# principal.net
KiCad netlist of a schematic drawn in Altium Designer
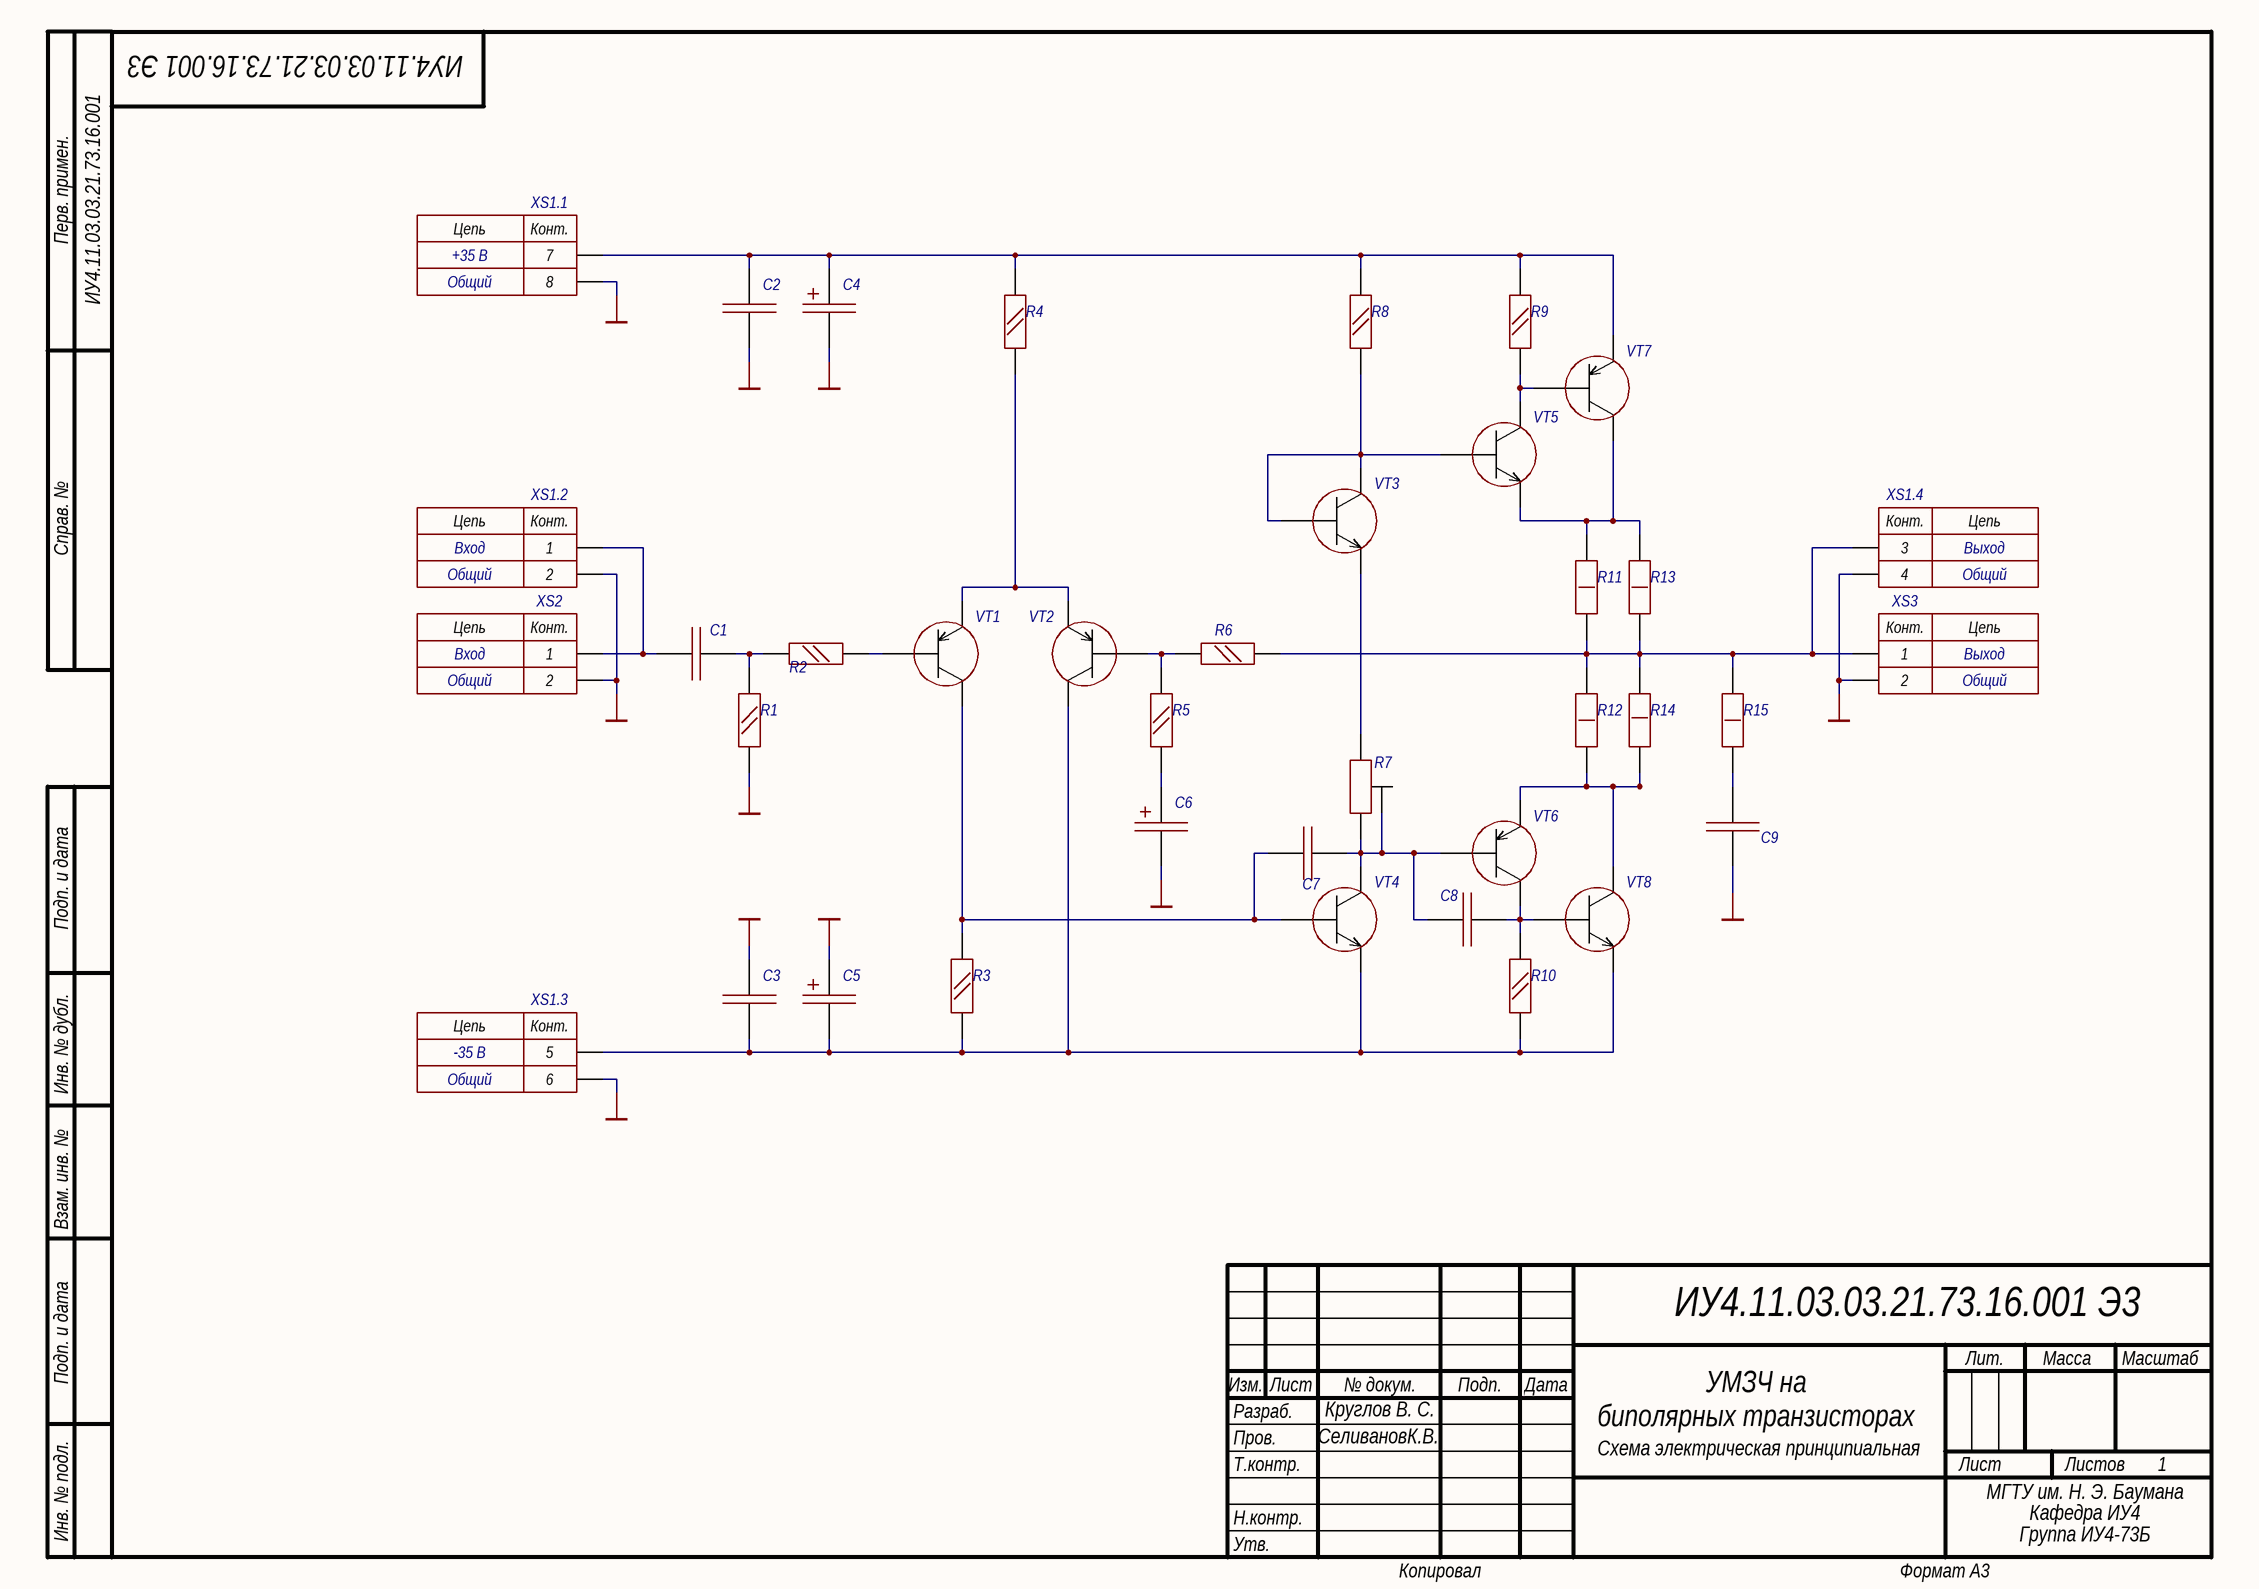
[diagram p0: principal.SchDoc]

(export (version "E")
  (design (tool "Eeschema 10.0.6"))
  (components
    (comp (ref "C1")
      (value "Capacitor")
      (footprint "CAP: 0805")
      (libsource (lib "Integrated_Library_PAAF") (part "Capacitor"))
    )
    (comp (ref "C2")
      (value "Capacitor")
      (footprint "CAP: 0805")
      (libsource (lib "Integrated_Library_PAAF") (part "Capacitor"))
    )
    (comp (ref "C3")
      (value "Capacitor")
      (footprint "CAP: 0805")
      (libsource (lib "Integrated_Library_PAAF") (part "Capacitor"))
    )
    (comp (ref "C4")
      (value "Capactor polar")
      (footprint "CAP: TANTAL-D")
      (libsource (lib "Integrated_Library_PAAF") (part "Capactor polar"))
    )
    (comp (ref "C5")
      (value "Capactor polar")
      (footprint "CAP: TANTAL-D")
      (libsource (lib "Integrated_Library_PAAF") (part "Capactor polar"))
    )
    (comp (ref "C6")
      (value "Capactor polar")
      (footprint "CAP: TANTAL-D")
      (libsource (lib "Integrated_Library_PAAF") (part "Capactor polar"))
    )
    (comp (ref "C7")
      (value "Capacitor")
      (footprint "CAP: 0805")
      (libsource (lib "Integrated_Library_PAAF") (part "Capacitor"))
    )
    (comp (ref "C8")
      (value "Capacitor")
      (footprint "CAP: 0805")
      (libsource (lib "Integrated_Library_PAAF") (part "Capacitor"))
    )
    (comp (ref "C9")
      (value "Capacitor")
      (footprint "CAP: 0805")
      (libsource (lib "Integrated_Library_PAAF") (part "Capacitor"))
    )
    (comp (ref "R1")
      (value "Resistor")
      (footprint "RES: 0805")
      (fields (field (name "TOLERANCE") "5%"))
      (libsource (lib "Sch") (part "Resistor"))
    )
    (comp (ref "R2")
      (value "Resistor")
      (footprint "RES: 0805")
      (fields (field (name "TOLERANCE") "5%"))
      (libsource (lib "") (part "Resistor_1"))
    )
    (comp (ref "R3")
      (value "Resistor")
      (footprint "RES: 0805")
      (fields (field (name "TOLERANCE") "5%"))
      (libsource (lib "Sch") (part "Resistor"))
    )
    (comp (ref "R4")
      (value "Resistor")
      (footprint "RES: 0805")
      (fields (field (name "TOLERANCE") "5%"))
      (libsource (lib "Sch") (part "Resistor"))
    )
    (comp (ref "R5")
      (value "Resistor")
      (footprint "RES: 0805")
      (fields (field (name "TOLERANCE") "5%"))
      (libsource (lib "Sch") (part "Resistor"))
    )
    (comp (ref "R6")
      (value "Resistor")
      (footprint "RES: 0805")
      (fields (field (name "TOLERANCE") "5%"))
      (libsource (lib "") (part "Resistor_1"))
    )
    (comp (ref "R7")
      (value "POT")
      (footprint "POT_3296W")
      (libsource (lib "Integrated_Library_PAAF") (part "POT"))
    )
    (comp (ref "R8")
      (value "Resistor")
      (footprint "RES: 0805")
      (fields (field (name "TOLERANCE") "5%"))
      (libsource (lib "Sch") (part "Resistor"))
    )
    (comp (ref "R9")
      (value "Resistor")
      (footprint "RES: 0805")
      (fields (field (name "TOLERANCE") "5%"))
      (libsource (lib "") (part "Resistor_2"))
    )
    (comp (ref "R10")
      (value "Resistor")
      (footprint "RES: 0805")
      (fields (field (name "TOLERANCE") "5%"))
      (libsource (lib "Sch") (part "Resistor"))
    )
    (comp (ref "R11")
      (value "Resistor")
      (footprint "RES: 2512")
      (fields (field (name "TOLERANCE") "5%"))
      (libsource (lib "Sch") (part "Resistor"))
    )
    (comp (ref "R12")
      (value "Resistor")
      (footprint "RES: 2512")
      (fields (field (name "TOLERANCE") "5%"))
      (libsource (lib "Sch") (part "Resistor"))
    )
    (comp (ref "R13")
      (value "Resistor")
      (footprint "RES: 2512")
      (fields (field (name "TOLERANCE") "5%"))
      (libsource (lib "Sch") (part "Resistor"))
    )
    (comp (ref "R14")
      (value "Resistor")
      (footprint "RES: 2512")
      (fields (field (name "TOLERANCE") "5%"))
      (libsource (lib "Sch") (part "Resistor"))
    )
    (comp (ref "R15")
      (value "Resistor")
      (footprint "RES: 2512")
      (fields (field (name "TOLERANCE") "5%"))
      (libsource (lib "Sch") (part "Resistor"))
    )
    (comp (ref "VT1")
      (value "Transistor_PNP")
      (footprint "TO92_3FB")
      (libsource (lib "Sch") (part "Transistor_PNP"))
    )
    (comp (ref "VT2")
      (value "Transistor_PNP")
      (footprint "TO92_3FB")
      (libsource (lib "Sch") (part "Transistor_PNP"))
    )
    (comp (ref "VT3")
      (value "BD139G")
      (footprint "TO126_3")
      (libsource (lib "Components - 07.07.24 - 21.07") (part "Transistor_NPN"))
    )
    (comp (ref "VT4")
      (value "BD139G")
      (footprint "TO220_3")
      (libsource (lib "Components - 07.07.24 - 21.07") (part "Transistor_NPN"))
    )
    (comp (ref "VT5")
      (value "BD139G")
      (footprint "TO126_3")
      (libsource (lib "Components - 07.07.24 - 21.07") (part "Transistor_NPN"))
    )
    (comp (ref "VT6")
      (value "Transistor_PNP")
      (footprint "TO126_3")
      (libsource (lib "Sch") (part "Transistor_PNP"))
    )
    (comp (ref "VT7")
      (value "Transistor_PNP")
      (footprint "TO247_3")
      (libsource (lib "Sch") (part "Transistor_PNP"))
    )
    (comp (ref "VT8")
      (value "BD139G")
      (footprint "TO247_3")
      (libsource (lib "Components - 07.07.24 - 21.07") (part "Transistor_NPN"))
    )
    (comp (ref "XP1") (value "CONN") (footprint "MOLEX_430450821") (libsource (lib "Sch") (part "CONN")))
    (comp (ref "XS1") (value "Audio") (footprint "FP-NMJ4HFD2-MFG") (libsource (lib "Sch") (part "Audio")))
    (comp (ref "XS2") (value "Audio") (footprint "FP-NMJ4HFD2-MFG") (libsource (lib "Sch") (part "Audio")))
  )
  (nets
    (net (code "1") (name "GND") (class "Default")
      (node (ref "C2") (pin "1") (pinfunction "1_1") (pintype "passive"))
      (node (ref "C3") (pin "2") (pinfunction "2_2") (pintype "passive"))
      (node (ref "C4") (pin "1") (pinfunction "1_1") (pintype "passive"))
      (node (ref "C5") (pin "2") (pinfunction "2_2") (pintype "passive"))
      (node (ref "C6") (pin "1") (pinfunction "1_1") (pintype "passive"))
      (node (ref "C9") (pin "2") (pinfunction "2_2") (pintype "passive"))
      (node (ref "R1") (pin "2") (pinfunction "2_2") (pintype "passive"))
      (node (ref "XP1") (pin "2") (pintype "passive"))
      (node (ref "XP1") (pin "4") (pintype "passive"))
      (node (ref "XP1") (pin "6") (pintype "passive"))
      (node (ref "XP1") (pin "8") (pintype "passive"))
      (node (ref "XS1") (pin "2") (pintype "passive"))
      (node (ref "XS2") (pin "2") (pintype "passive"))
    )
    (net (code "2") (name "Net-(C1-Pad1)") (class "Default")
      (node (ref "C1") (pin "1") (pinfunction "1_1") (pintype "passive"))
      (node (ref "XP1") (pin "1") (pintype "passive"))
      (node (ref "XS1") (pin "1") (pintype "passive"))
    )
    (net (code "3") (name "Net-(C1-Pad2)") (class "Default")
      (node (ref "C1") (pin "2") (pinfunction "2_2") (pintype "passive"))
      (node (ref "R1") (pin "1") (pinfunction "1_1") (pintype "passive"))
      (node (ref "R2") (pin "1") (pinfunction "1_1") (pintype "passive"))
    )
    (net (code "4") (name "Net-(C6-Pad2)") (class "Default")
      (node (ref "C6") (pin "2") (pinfunction "2_2") (pintype "passive"))
      (node (ref "R5") (pin "2") (pinfunction "2_2") (pintype "passive"))
    )
    (net (code "5") (name "Net-(C9-Pad1)") (class "Default")
      (node (ref "C9") (pin "1") (pinfunction "1_1") (pintype "passive"))
      (node (ref "R15") (pin "2") (pinfunction "2_2") (pintype "passive"))
    )
    (net (code "6") (name "Net-(R11-Pad2)") (class "Default")
      (node (ref "R11") (pin "2") (pinfunction "2_2") (pintype "passive"))
      (node (ref "R12") (pin "1") (pinfunction "1_1") (pintype "passive"))
      (node (ref "R13") (pin "2") (pinfunction "2_2") (pintype "passive"))
      (node (ref "R14") (pin "1") (pinfunction "1_1") (pintype "passive"))
      (node (ref "R15") (pin "1") (pinfunction "1_1") (pintype "passive"))
      (node (ref "R6") (pin "2") (pinfunction "2_2") (pintype "passive"))
      (node (ref "XP1") (pin "3") (pintype "passive"))
      (node (ref "XS2") (pin "1") (pintype "passive"))
    )
    (net (code "7") (name "Net-(VT1-B)") (class "Default")
      (node (ref "R2") (pin "2") (pinfunction "2_2") (pintype "passive"))
      (node (ref "VT1") (pin "3") (pinfunction "B_3") (pintype "passive"))
    )
    (net (code "8") (name "Net-(VT1-C)") (class "Default")
      (node (ref "C7") (pin "1") (pinfunction "1_1") (pintype "passive"))
      (node (ref "R3") (pin "1") (pinfunction "1_1") (pintype "passive"))
      (node (ref "VT1") (pin "2") (pinfunction "C_2") (pintype "passive"))
      (node (ref "VT4") (pin "3") (pinfunction "B_3") (pintype "passive"))
    )
    (net (code "9") (name "Net-(VT1-E)") (class "Default")
      (node (ref "R4") (pin "2") (pinfunction "2_2") (pintype "passive"))
      (node (ref "VT1") (pin "1") (pinfunction "E_1") (pintype "passive"))
      (node (ref "VT2") (pin "1") (pinfunction "E_1") (pintype "passive"))
    )
    (net (code "10") (name "Net-(VT2-B)") (class "Default")
      (node (ref "R5") (pin "1") (pinfunction "1_1") (pintype "passive"))
      (node (ref "R6") (pin "1") (pinfunction "1_1") (pintype "passive"))
      (node (ref "VT2") (pin "3") (pinfunction "B_3") (pintype "passive"))
    )
    (net (code "11") (name "Net-(VT2-C)") (class "Default")
      (node (ref "C3") (pin "1") (pinfunction "1_1") (pintype "passive"))
      (node (ref "C5") (pin "1") (pinfunction "1_1") (pintype "passive"))
      (node (ref "R10") (pin "2") (pinfunction "2_2") (pintype "passive"))
      (node (ref "R3") (pin "2") (pinfunction "2_2") (pintype "passive"))
      (node (ref "VT2") (pin "2") (pinfunction "C_2") (pintype "passive"))
      (node (ref "VT4") (pin "1") (pinfunction "E_1") (pintype "passive"))
      (node (ref "VT8") (pin "1") (pinfunction "E_1") (pintype "passive"))
      (node (ref "XP1") (pin "5") (pintype "passive"))
    )
    (net (code "12") (name "Net-(VT3-B)") (class "Default")
      (node (ref "R8") (pin "2") (pinfunction "2_2") (pintype "passive"))
      (node (ref "VT3") (pin "2") (pinfunction "C_2") (pintype "passive"))
      (node (ref "VT3") (pin "3") (pinfunction "B_3") (pintype "passive"))
      (node (ref "VT5") (pin "3") (pinfunction "B_3") (pintype "passive"))
    )
    (net (code "13") (name "Net-(VT3-E)") (class "Default")
      (node (ref "R7") (pin "1") (pinfunction "1_1") (pintype "passive"))
      (node (ref "VT3") (pin "1") (pinfunction "E_1") (pintype "passive"))
    )
    (net (code "14") (name "Net-(VT4-C)") (class "Default")
      (node (ref "C7") (pin "2") (pinfunction "2_2") (pintype "passive"))
      (node (ref "C8") (pin "1") (pinfunction "1_1") (pintype "passive"))
      (node (ref "R7") (pin "2") (pinfunction "2_2") (pintype "passive"))
      (node (ref "R7") (pin "3") (pinfunction "3_3") (pintype "passive"))
      (node (ref "VT4") (pin "2") (pinfunction "C_2") (pintype "passive"))
      (node (ref "VT6") (pin "3") (pinfunction "B_3") (pintype "passive"))
    )
    (net (code "15") (name "Net-(VT5-C)") (class "Default")
      (node (ref "R9") (pin "1") (pinfunction "1_1") (pintype "passive"))
      (node (ref "VT5") (pin "2") (pinfunction "C_2") (pintype "passive"))
      (node (ref "VT7") (pin "3") (pinfunction "B_3") (pintype "passive"))
    )
    (net (code "16") (name "Net-(VT5-E)") (class "Default")
      (node (ref "R11") (pin "1") (pinfunction "1_1") (pintype "passive"))
      (node (ref "R13") (pin "1") (pinfunction "1_1") (pintype "passive"))
      (node (ref "VT5") (pin "1") (pinfunction "E_1") (pintype "passive"))
      (node (ref "VT7") (pin "2") (pinfunction "C_2") (pintype "passive"))
    )
    (net (code "17") (name "Net-(VT6-C)") (class "Default")
      (node (ref "C8") (pin "2") (pinfunction "2_2") (pintype "passive"))
      (node (ref "R10") (pin "1") (pinfunction "1_1") (pintype "passive"))
      (node (ref "VT6") (pin "2") (pinfunction "C_2") (pintype "passive"))
      (node (ref "VT8") (pin "3") (pinfunction "B_3") (pintype "passive"))
    )
    (net (code "18") (name "Net-(VT6-E)") (class "Default")
      (node (ref "R12") (pin "2") (pinfunction "2_2") (pintype "passive"))
      (node (ref "R14") (pin "2") (pinfunction "2_2") (pintype "passive"))
      (node (ref "VT6") (pin "1") (pinfunction "E_1") (pintype "passive"))
      (node (ref "VT8") (pin "2") (pinfunction "C_2") (pintype "passive"))
    )
    (net (code "19") (name "Net-(VT7-E)") (class "Default")
      (node (ref "C2") (pin "2") (pinfunction "2_2") (pintype "passive"))
      (node (ref "C4") (pin "2") (pinfunction "2_2") (pintype "passive"))
      (node (ref "R4") (pin "1") (pinfunction "1_1") (pintype "passive"))
      (node (ref "R8") (pin "1") (pinfunction "1_1") (pintype "passive"))
      (node (ref "R9") (pin "2") (pinfunction "2_2") (pintype "passive"))
      (node (ref "VT7") (pin "1") (pinfunction "E_1") (pintype "passive"))
      (node (ref "XP1") (pin "7") (pintype "passive"))
    )
  )
)
